# STM32_IO.net
KiCad netlist of a schematic drawn in Altium Designer
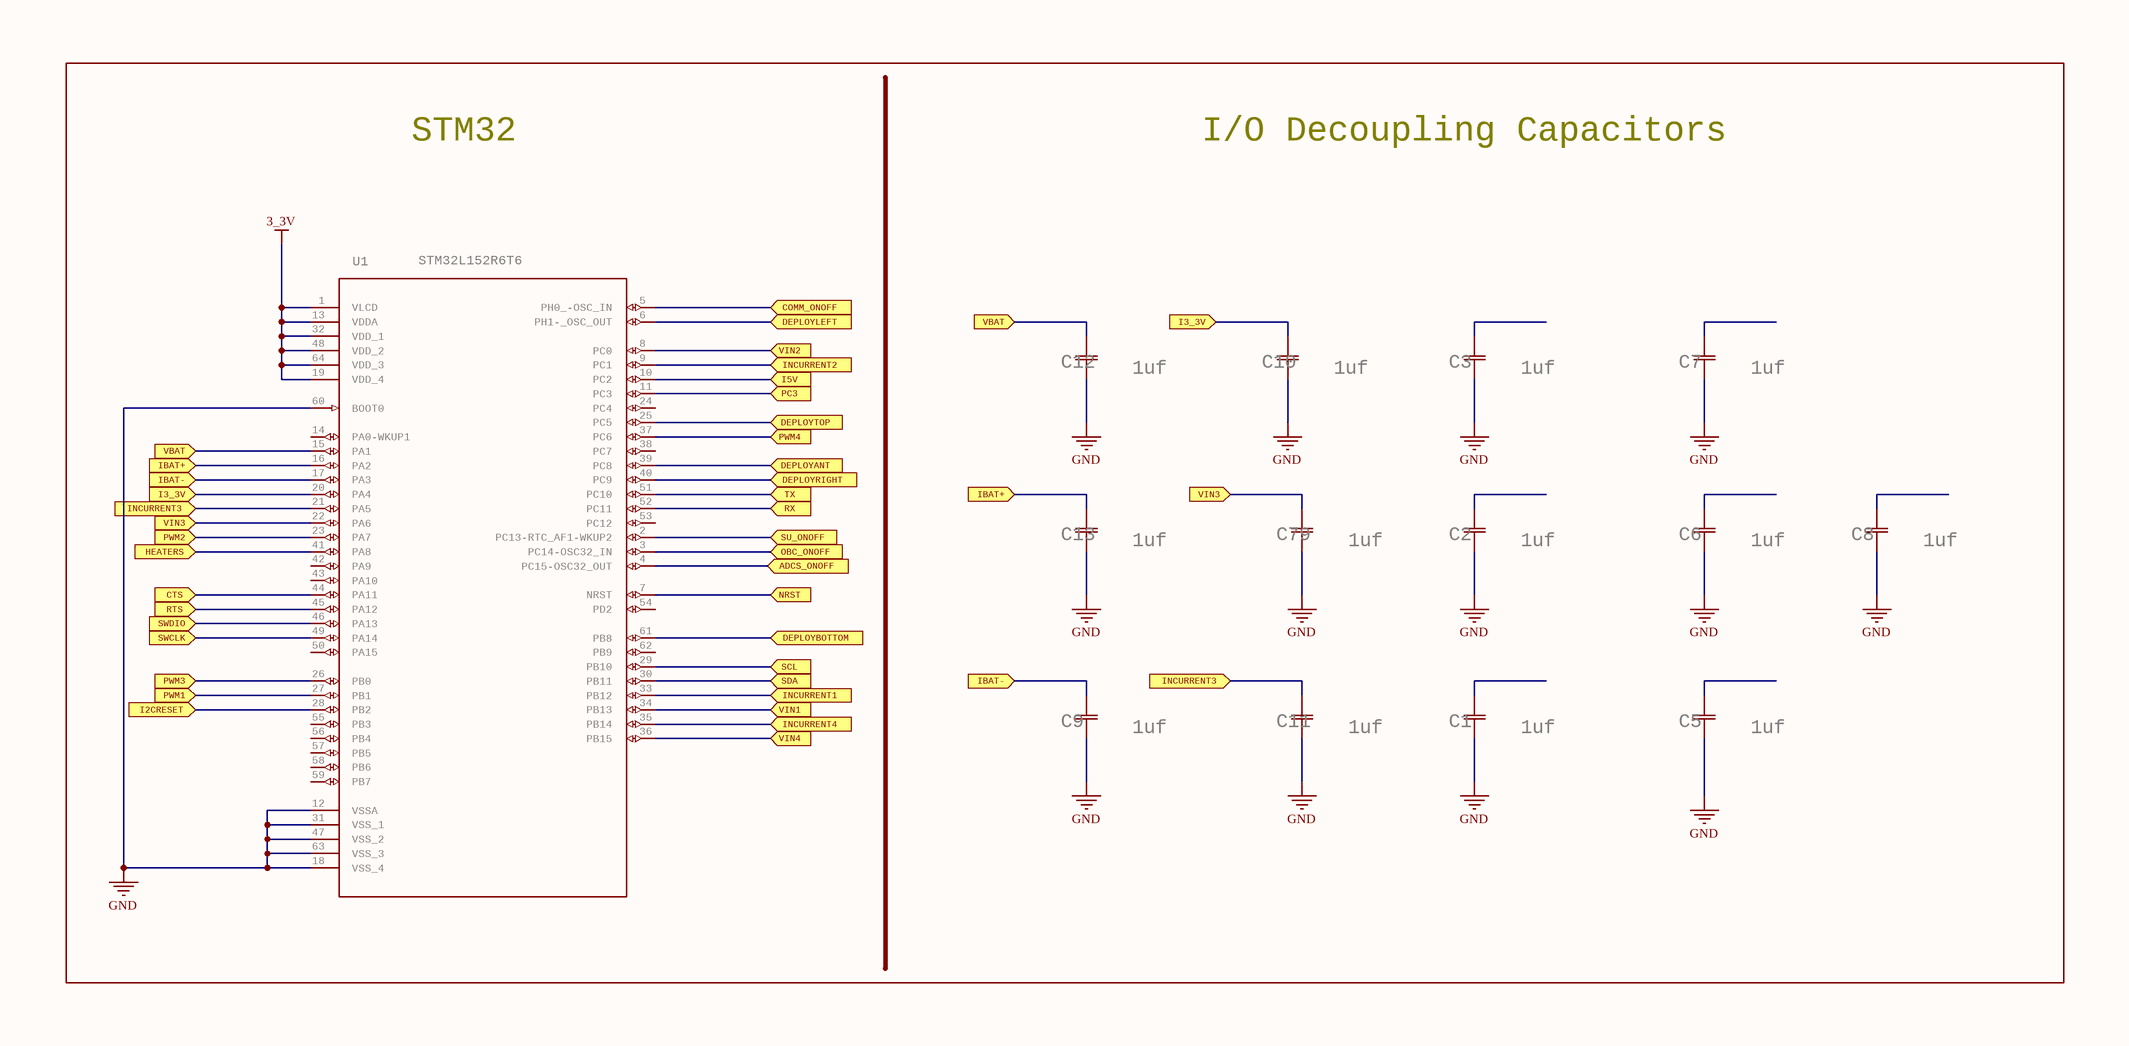
[diagram p0: STM32_IO.SchDoc]

(export (version "E")
  (design (tool "Eeschema 10.0.6"))
  (components
    (comp (ref "C1")
      (value "1uf")
      (footprint "YAG_CC0603_YAG-L")
      (fields (field (name "MANUFACTURER_PART_NUMBER") "CC0603KRX7R7BB105"))
      (libsource (lib "Cap 1uf") (part "CC0603KRX7R7BB105YAG_CC0603_YAG-L"))
    )
    (comp (ref "C2")
      (value "1uf")
      (footprint "YAG_CC0603_YAG-L")
      (fields (field (name "MANUFACTURER_PART_NUMBER") "CC0603KRX7R7BB105"))
      (libsource (lib "Cap 1uf") (part "CC0603KRX7R7BB105YAG_CC0603_YAG-L"))
    )
    (comp (ref "C3")
      (value "1uf")
      (footprint "YAG_CC0603_YAG-L")
      (fields (field (name "MANUFACTURER_PART_NUMBER") "CC0603KRX7R7BB105"))
      (libsource (lib "Cap 1uf") (part "CC0603KRX7R7BB105YAG_CC0603_YAG-L"))
    )
    (comp (ref "C5")
      (value "1uf")
      (footprint "YAG_CC0603_YAG-L")
      (fields (field (name "MANUFACTURER_PART_NUMBER") "CC0603KRX7R7BB105"))
      (libsource (lib "Cap 1uf") (part "CC0603KRX7R7BB105YAG_CC0603_YAG-L"))
    )
    (comp (ref "C6")
      (value "1uf")
      (footprint "YAG_CC0603_YAG-L")
      (fields (field (name "MANUFACTURER_PART_NUMBER") "CC0603KRX7R7BB105"))
      (libsource (lib "Cap 1uf") (part "CC0603KRX7R7BB105YAG_CC0603_YAG-L"))
    )
    (comp (ref "C7")
      (value "1uf")
      (footprint "YAG_CC0603_YAG-L")
      (fields (field (name "MANUFACTURER_PART_NUMBER") "CC0603KRX7R7BB105"))
      (libsource (lib "Cap 1uf") (part "CC0603KRX7R7BB105YAG_CC0603_YAG-L"))
    )
    (comp (ref "C8")
      (value "1uf")
      (footprint "YAG_CC0603_YAG-L")
      (fields (field (name "MANUFACTURER_PART_NUMBER") "CC0603KRX7R7BB105"))
      (libsource (lib "Cap 1uf") (part "CC0603KRX7R7BB105YAG_CC0603_YAG-L"))
    )
    (comp (ref "C9")
      (value "1uf")
      (footprint "YAG_CC0603_YAG-L")
      (fields (field (name "MANUFACTURER_PART_NUMBER") "CC0603KRX7R7BB105"))
      (libsource (lib "Cap 1uf") (part "CC0603KRX7R7BB105YAG_CC0603_YAG-L"))
    )
    (comp (ref "C10")
      (value "1uf")
      (footprint "YAG_CC0603_YAG-L")
      (fields (field (name "MANUFACTURER_PART_NUMBER") "CC0603KRX7R7BB105"))
      (libsource (lib "Cap 1uf") (part "CC0603KRX7R7BB105YAG_CC0603_YAG-L"))
    )
    (comp (ref "C11")
      (value "1uf")
      (footprint "YAG_CC0603_YAG-L")
      (fields (field (name "MANUFACTURER_PART_NUMBER") "CC0603KRX7R7BB105"))
      (libsource (lib "Cap 1uf") (part "CC0603KRX7R7BB105YAG_CC0603_YAG-L"))
    )
    (comp (ref "C12")
      (value "1uf")
      (footprint "YAG_CC0603_YAG-L")
      (fields (field (name "MANUFACTURER_PART_NUMBER") "CC0603KRX7R7BB105"))
      (libsource (lib "Cap 1uf") (part "CC0603KRX7R7BB105YAG_CC0603_YAG-L"))
    )
    (comp (ref "C13")
      (value "1uf")
      (footprint "YAG_CC0603_YAG-L")
      (fields (field (name "MANUFACTURER_PART_NUMBER") "CC0603KRX7R7BB105"))
      (libsource (lib "Cap 1uf") (part "CC0603KRX7R7BB105YAG_CC0603_YAG-L"))
    )
    (comp (ref "C79")
      (value "1uf")
      (footprint "YAG_CC0603_YAG-L")
      (fields (field (name "MANUFACTURER_PART_NUMBER") "CC0603KRX7R7BB105"))
      (libsource (lib "Cap 1uf") (part "CC0603KRX7R7BB105YAG_CC0603_YAG-L"))
    )
    (comp (ref "U1")
      (value "STM32L152R6T6")
      (footprint "QFP50P1200X1200X160-64N")
      (description "Ultralow power ARM-based 32-bit MCU  Check prices")
      (fields (field (name "MF") "STMicroelectronics") (field (name "LIBRARYNAME") "STM32L152R6T6 replace"))
      (libsource (lib "STM32L152R6T6 replace") (part "STM32L152R6T6"))
    )
  )
  (nets
    (net (code "1") (name "/ADCS_ONOFF") (class "Default")
      (node (ref "U1") (pin "4") (pinfunction "PC15-OSC32_OUT_4") (pintype "bidirectional"))
    )
    (net (code "2") (name "/COMM_ONOFF") (class "Default")
      (node (ref "U1") (pin "5") (pinfunction "PH0_-OSC_IN_5") (pintype "bidirectional"))
    )
    (net (code "3") (name "/CTS") (class "Default")
      (node (ref "U1") (pin "44") (pinfunction "PA11_44") (pintype "bidirectional"))
    )
    (net (code "4") (name "/DEPLOYANT") (class "Default")
      (node (ref "U1") (pin "39") (pinfunction "PC8_39") (pintype "bidirectional"))
    )
    (net (code "5") (name "/DEPLOYBOTTOM") (class "Default")
      (node (ref "U1") (pin "61") (pinfunction "PB8_61") (pintype "bidirectional"))
    )
    (net (code "6") (name "/DEPLOYLEFT") (class "Default")
      (node (ref "U1") (pin "6") (pinfunction "PH1-_OSC_OUT_6") (pintype "bidirectional"))
    )
    (net (code "7") (name "/DEPLOYRIGHT") (class "Default")
      (node (ref "U1") (pin "40") (pinfunction "PC9_40") (pintype "bidirectional"))
    )
    (net (code "8") (name "/DEPLOYTOP") (class "Default")
      (node (ref "U1") (pin "25") (pinfunction "PC5_25") (pintype "bidirectional"))
    )
    (net (code "9") (name "/HEATERS") (class "Default")
      (node (ref "U1") (pin "41") (pinfunction "PA8_41") (pintype "bidirectional"))
    )
    (net (code "10") (name "/I2CRESET") (class "Default")
      (node (ref "U1") (pin "28") (pinfunction "PB2_28") (pintype "bidirectional"))
    )
    (net (code "11") (name "/I3_3V") (class "Default")
      (node (ref "C10") (pin "2") (pinfunction "2_2") (pintype "passive"))
      (node (ref "U1") (pin "20") (pinfunction "PA4_20") (pintype "bidirectional"))
    )
    (net (code "12") (name "/I5V") (class "Default")
      (node (ref "U1") (pin "10") (pinfunction "PC2_10") (pintype "bidirectional"))
    )
    (net (code "13") (name "/IBAT+") (class "Default")
      (node (ref "C13") (pin "2") (pinfunction "2_2") (pintype "passive"))
      (node (ref "U1") (pin "16") (pinfunction "PA2_16") (pintype "bidirectional"))
    )
    (net (code "14") (name "/IBAT-") (class "Default")
      (node (ref "C9") (pin "2") (pinfunction "2_2") (pintype "passive"))
      (node (ref "U1") (pin "17") (pinfunction "PA3_17") (pintype "bidirectional"))
    )
    (net (code "15") (name "/INCURRENT1") (class "Default")
      (node (ref "U1") (pin "33") (pinfunction "PB12_33") (pintype "bidirectional"))
    )
    (net (code "16") (name "/INCURRENT2") (class "Default")
      (node (ref "U1") (pin "9") (pinfunction "PC1_9") (pintype "bidirectional"))
    )
    (net (code "17") (name "/INCURRENT3") (class "Default")
      (node (ref "C11") (pin "2") (pinfunction "2_2") (pintype "passive"))
      (node (ref "U1") (pin "21") (pinfunction "PA5_21") (pintype "bidirectional"))
    )
    (net (code "18") (name "/INCURRENT4") (class "Default")
      (node (ref "U1") (pin "35") (pinfunction "PB14_35") (pintype "bidirectional"))
    )
    (net (code "19") (name "/NRST") (class "Default")
      (node (ref "U1") (pin "7") (pinfunction "NRST_7") (pintype "bidirectional"))
    )
    (net (code "20") (name "/OBC_ONOFF") (class "Default")
      (node (ref "U1") (pin "3") (pinfunction "PC14-OSC32_IN_3") (pintype "bidirectional"))
    )
    (net (code "21") (name "/PC3") (class "Default")
      (node (ref "U1") (pin "11") (pinfunction "PC3_11") (pintype "bidirectional"))
    )
    (net (code "22") (name "/PWM1") (class "Default")
      (node (ref "U1") (pin "27") (pinfunction "PB1_27") (pintype "bidirectional"))
    )
    (net (code "23") (name "/PWM2") (class "Default")
      (node (ref "U1") (pin "23") (pinfunction "PA7_23") (pintype "bidirectional"))
    )
    (net (code "24") (name "/PWM3") (class "Default")
      (node (ref "U1") (pin "26") (pinfunction "PB0_26") (pintype "bidirectional"))
    )
    (net (code "25") (name "/PWM4") (class "Default")
      (node (ref "U1") (pin "37") (pinfunction "PC6_37") (pintype "bidirectional"))
    )
    (net (code "26") (name "/RTS") (class "Default")
      (node (ref "U1") (pin "45") (pinfunction "PA12_45") (pintype "bidirectional"))
    )
    (net (code "27") (name "/RX") (class "Default")
      (node (ref "U1") (pin "52") (pinfunction "PC11_52") (pintype "bidirectional"))
    )
    (net (code "28") (name "/SCL") (class "Default")
      (node (ref "U1") (pin "29") (pinfunction "PB10_29") (pintype "bidirectional"))
    )
    (net (code "29") (name "/SDA") (class "Default")
      (node (ref "U1") (pin "30") (pinfunction "PB11_30") (pintype "bidirectional"))
    )
    (net (code "30") (name "/SU_ONOFF") (class "Default")
      (node (ref "U1") (pin "2") (pinfunction "PC13-RTC_AF1-WKUP2_2") (pintype "bidirectional"))
    )
    (net (code "31") (name "/SWCLK") (class "Default")
      (node (ref "U1") (pin "49") (pinfunction "PA14_49") (pintype "bidirectional"))
    )
    (net (code "32") (name "/SWDIO") (class "Default")
      (node (ref "U1") (pin "46") (pinfunction "PA13_46") (pintype "bidirectional"))
    )
    (net (code "33") (name "/TX") (class "Default")
      (node (ref "U1") (pin "51") (pinfunction "PC10_51") (pintype "bidirectional"))
    )
    (net (code "34") (name "/VBAT") (class "Default")
      (node (ref "C12") (pin "2") (pinfunction "2_2") (pintype "passive"))
      (node (ref "U1") (pin "15") (pinfunction "PA1_15") (pintype "bidirectional"))
    )
    (net (code "35") (name "/VIN1") (class "Default")
      (node (ref "U1") (pin "34") (pinfunction "PB13_34") (pintype "bidirectional"))
    )
    (net (code "36") (name "/VIN2") (class "Default")
      (node (ref "U1") (pin "8") (pinfunction "PC0_8") (pintype "bidirectional"))
    )
    (net (code "37") (name "/VIN3") (class "Default")
      (node (ref "C79") (pin "2") (pinfunction "2_2") (pintype "passive"))
      (node (ref "U1") (pin "22") (pinfunction "PA6_22") (pintype "bidirectional"))
    )
    (net (code "38") (name "/VIN4") (class "Default")
      (node (ref "U1") (pin "36") (pinfunction "PB15_36") (pintype "bidirectional"))
    )
    (net (code "39") (name "3_3V") (class "Default")
      (node (ref "U1") (pin "1") (pinfunction "VLCD_1") (pintype "power_in"))
      (node (ref "U1") (pin "13") (pinfunction "VDDA_13") (pintype "power_in"))
      (node (ref "U1") (pin "19") (pinfunction "VDD_4_19") (pintype "power_in"))
      (node (ref "U1") (pin "32") (pinfunction "VDD_1_32") (pintype "power_in"))
      (node (ref "U1") (pin "48") (pinfunction "VDD_2_48") (pintype "power_in"))
      (node (ref "U1") (pin "64") (pinfunction "VDD_3_64") (pintype "power_in"))
    )
    (net (code "40") (name "GND") (class "Default")
      (node (ref "C1") (pin "1") (pinfunction "1_1") (pintype "passive"))
      (node (ref "C10") (pin "1") (pinfunction "1_1") (pintype "passive"))
      (node (ref "C11") (pin "1") (pinfunction "1_1") (pintype "passive"))
      (node (ref "C12") (pin "1") (pinfunction "1_1") (pintype "passive"))
      (node (ref "C13") (pin "1") (pinfunction "1_1") (pintype "passive"))
      (node (ref "C2") (pin "1") (pinfunction "1_1") (pintype "passive"))
      (node (ref "C3") (pin "1") (pinfunction "1_1") (pintype "passive"))
      (node (ref "C5") (pin "1") (pinfunction "1_1") (pintype "passive"))
      (node (ref "C6") (pin "1") (pinfunction "1_1") (pintype "passive"))
      (node (ref "C7") (pin "1") (pinfunction "1_1") (pintype "passive"))
      (node (ref "C79") (pin "1") (pinfunction "1_1") (pintype "passive"))
      (node (ref "C8") (pin "1") (pinfunction "1_1") (pintype "passive"))
      (node (ref "C9") (pin "1") (pinfunction "1_1") (pintype "passive"))
      (node (ref "U1") (pin "12") (pinfunction "VSSA_12") (pintype "power_in"))
      (node (ref "U1") (pin "18") (pinfunction "VSS_4_18") (pintype "power_in"))
      (node (ref "U1") (pin "31") (pinfunction "VSS_1_31") (pintype "power_in"))
      (node (ref "U1") (pin "47") (pinfunction "VSS_2_47") (pintype "power_in"))
      (node (ref "U1") (pin "60") (pinfunction "BOOT0_60") (pintype "input"))
      (node (ref "U1") (pin "63") (pinfunction "VSS_3_63") (pintype "power_in"))
    )
    (net (code "41") (name "unconnected-(C1-Pad2)") (class "Default")
      (node (ref "C1") (pin "2") (pinfunction "2_2") (pintype "passive"))
    )
    (net (code "42") (name "unconnected-(C2-Pad2)") (class "Default")
      (node (ref "C2") (pin "2") (pinfunction "2_2") (pintype "passive"))
    )
    (net (code "43") (name "unconnected-(C3-Pad2)") (class "Default")
      (node (ref "C3") (pin "2") (pinfunction "2_2") (pintype "passive"))
    )
    (net (code "44") (name "unconnected-(C5-Pad2)") (class "Default")
      (node (ref "C5") (pin "2") (pinfunction "2_2") (pintype "passive"))
    )
    (net (code "45") (name "unconnected-(C6-Pad2)") (class "Default")
      (node (ref "C6") (pin "2") (pinfunction "2_2") (pintype "passive"))
    )
    (net (code "46") (name "unconnected-(C7-Pad2)") (class "Default")
      (node (ref "C7") (pin "2") (pinfunction "2_2") (pintype "passive"))
    )
    (net (code "47") (name "unconnected-(C8-Pad2)") (class "Default")
      (node (ref "C8") (pin "2") (pinfunction "2_2") (pintype "passive"))
    )
    (net (code "48") (name "unconnected-(U1-PA0-WKUP1-Pad14)") (class "Default")
      (node (ref "U1") (pin "14") (pinfunction "PA0-WKUP1_14") (pintype "bidirectional"))
    )
    (net (code "49") (name "unconnected-(U1-PA9-Pad42)") (class "Default")
      (node (ref "U1") (pin "42") (pinfunction "PA9_42") (pintype "bidirectional"))
    )
    (net (code "50") (name "unconnected-(U1-PA10-Pad43)") (class "Default")
      (node (ref "U1") (pin "43") (pinfunction "PA10_43") (pintype "bidirectional"))
    )
    (net (code "51") (name "unconnected-(U1-PA15-Pad50)") (class "Default")
      (node (ref "U1") (pin "50") (pinfunction "PA15_50") (pintype "bidirectional"))
    )
    (net (code "52") (name "unconnected-(U1-PB3-Pad55)") (class "Default")
      (node (ref "U1") (pin "55") (pinfunction "PB3_55") (pintype "bidirectional"))
    )
    (net (code "53") (name "unconnected-(U1-PB4-Pad56)") (class "Default")
      (node (ref "U1") (pin "56") (pinfunction "PB4_56") (pintype "bidirectional"))
    )
    (net (code "54") (name "unconnected-(U1-PB5-Pad57)") (class "Default")
      (node (ref "U1") (pin "57") (pinfunction "PB5_57") (pintype "bidirectional"))
    )
    (net (code "55") (name "unconnected-(U1-PB6-Pad58)") (class "Default")
      (node (ref "U1") (pin "58") (pinfunction "PB6_58") (pintype "bidirectional"))
    )
    (net (code "56") (name "unconnected-(U1-PB7-Pad59)") (class "Default")
      (node (ref "U1") (pin "59") (pinfunction "PB7_59") (pintype "bidirectional"))
    )
    (net (code "57") (name "unconnected-(U1-PB9-Pad62)") (class "Default")
      (node (ref "U1") (pin "62") (pinfunction "PB9_62") (pintype "bidirectional"))
    )
    (net (code "58") (name "unconnected-(U1-PC4-Pad24)") (class "Default")
      (node (ref "U1") (pin "24") (pinfunction "PC4_24") (pintype "bidirectional"))
    )
    (net (code "59") (name "unconnected-(U1-PC7-Pad38)") (class "Default")
      (node (ref "U1") (pin "38") (pinfunction "PC7_38") (pintype "bidirectional"))
    )
    (net (code "60") (name "unconnected-(U1-PC12-Pad53)") (class "Default")
      (node (ref "U1") (pin "53") (pinfunction "PC12_53") (pintype "bidirectional"))
    )
    (net (code "61") (name "unconnected-(U1-PD2-Pad54)") (class "Default")
      (node (ref "U1") (pin "54") (pinfunction "PD2_54") (pintype "bidirectional"))
    )
  )
)
